# Single_Encoder_Breakout.net
KiCad netlist of a schematic drawn in EAGLE
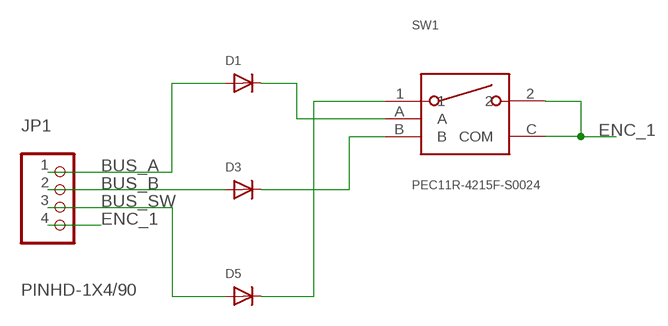
[diagram p0: schematic, sheet 1]

(export (version "E")
  (design (tool "Eeschema 10.0.6"))
  (components
    (comp (ref "D1")
      (value "DIODESOD-123")
      (footprint "eagle-import:SOD-123")
      (libsource (lib "eagle-import") (part "DIODESOD-123"))
    )
    (comp (ref "D3")
      (value "DIODESOD-123")
      (footprint "eagle-import:SOD-123")
      (libsource (lib "eagle-import") (part "DIODESOD-123"))
    )
    (comp (ref "D5")
      (value "DIODESOD-123")
      (footprint "eagle-import:SOD-123")
      (libsource (lib "eagle-import") (part "DIODESOD-123"))
    )
    (comp (ref "JP1")
      (value "PINHD-1X4/90")
      (footprint "eagle-import:1X04_90")
      (libsource (lib "eagle-import") (part "PINHD-1X4/90"))
    )
    (comp (ref "SW1")
      (value "PEC11R-4215F-S0024")
      (footprint "eagle-import:PEC11R-4215F-S0024")
      (fields
        (field (name "DIGIKEY_PART_NUMBER") "PEC11R-4215F-S0024-ND")
        (field (name "MANUFACTURER") "Bourns Inc.")
        (field (name "CREATED_BY") "PCBLayout.com")
      )
      (libsource (lib "eagle-import") (part "PEC11R-4215F-S0024"))
    )
  )
  (nets
    (net (code "1") (name "/BUS_A") (class "Default")
      (node (ref "D1") (pin "A") (pinfunction "A_A") (pintype "passive"))
      (node (ref "JP1") (pin "1") (pinfunction "1_1") (pintype "passive"))
    )
    (net (code "2") (name "/BUS_B") (class "Default")
      (node (ref "D3") (pin "A") (pinfunction "A_A") (pintype "passive"))
      (node (ref "JP1") (pin "2") (pinfunction "2_2") (pintype "passive"))
    )
    (net (code "3") (name "/BUS_SW") (class "Default")
      (node (ref "D5") (pin "A") (pinfunction "A_A") (pintype "passive"))
      (node (ref "JP1") (pin "3") (pinfunction "3_3") (pintype "passive"))
    )
    (net (code "4") (name "/ENC_1") (class "Default")
      (node (ref "JP1") (pin "4") (pinfunction "4_4") (pintype "passive"))
      (node (ref "SW1") (pin "2") (pinfunction "2_2") (pintype "passive"))
      (node (ref "SW1") (pin "C") (pinfunction "COM_C") (pintype "passive"))
    )
    (net (code "5") (name "Net-(D1-PadC)") (class "Default")
      (node (ref "D1") (pin "C") (pinfunction "C_C") (pintype "passive"))
      (node (ref "SW1") (pin "A") (pinfunction "A_A") (pintype "passive"))
    )
    (net (code "6") (name "Net-(D3-PadC)") (class "Default")
      (node (ref "D3") (pin "C") (pinfunction "C_C") (pintype "passive"))
      (node (ref "SW1") (pin "B") (pinfunction "B_B") (pintype "passive"))
    )
    (net (code "7") (name "Net-(D5-PadC)") (class "Default")
      (node (ref "D5") (pin "C") (pinfunction "C_C") (pintype "passive"))
      (node (ref "SW1") (pin "1") (pinfunction "1_1") (pintype "passive"))
    )
  )
)
